# SCH_SemaforkyNG_v2_0_2023-06-26.net
KiCad netlist of a schematic drawn in EasyEDA
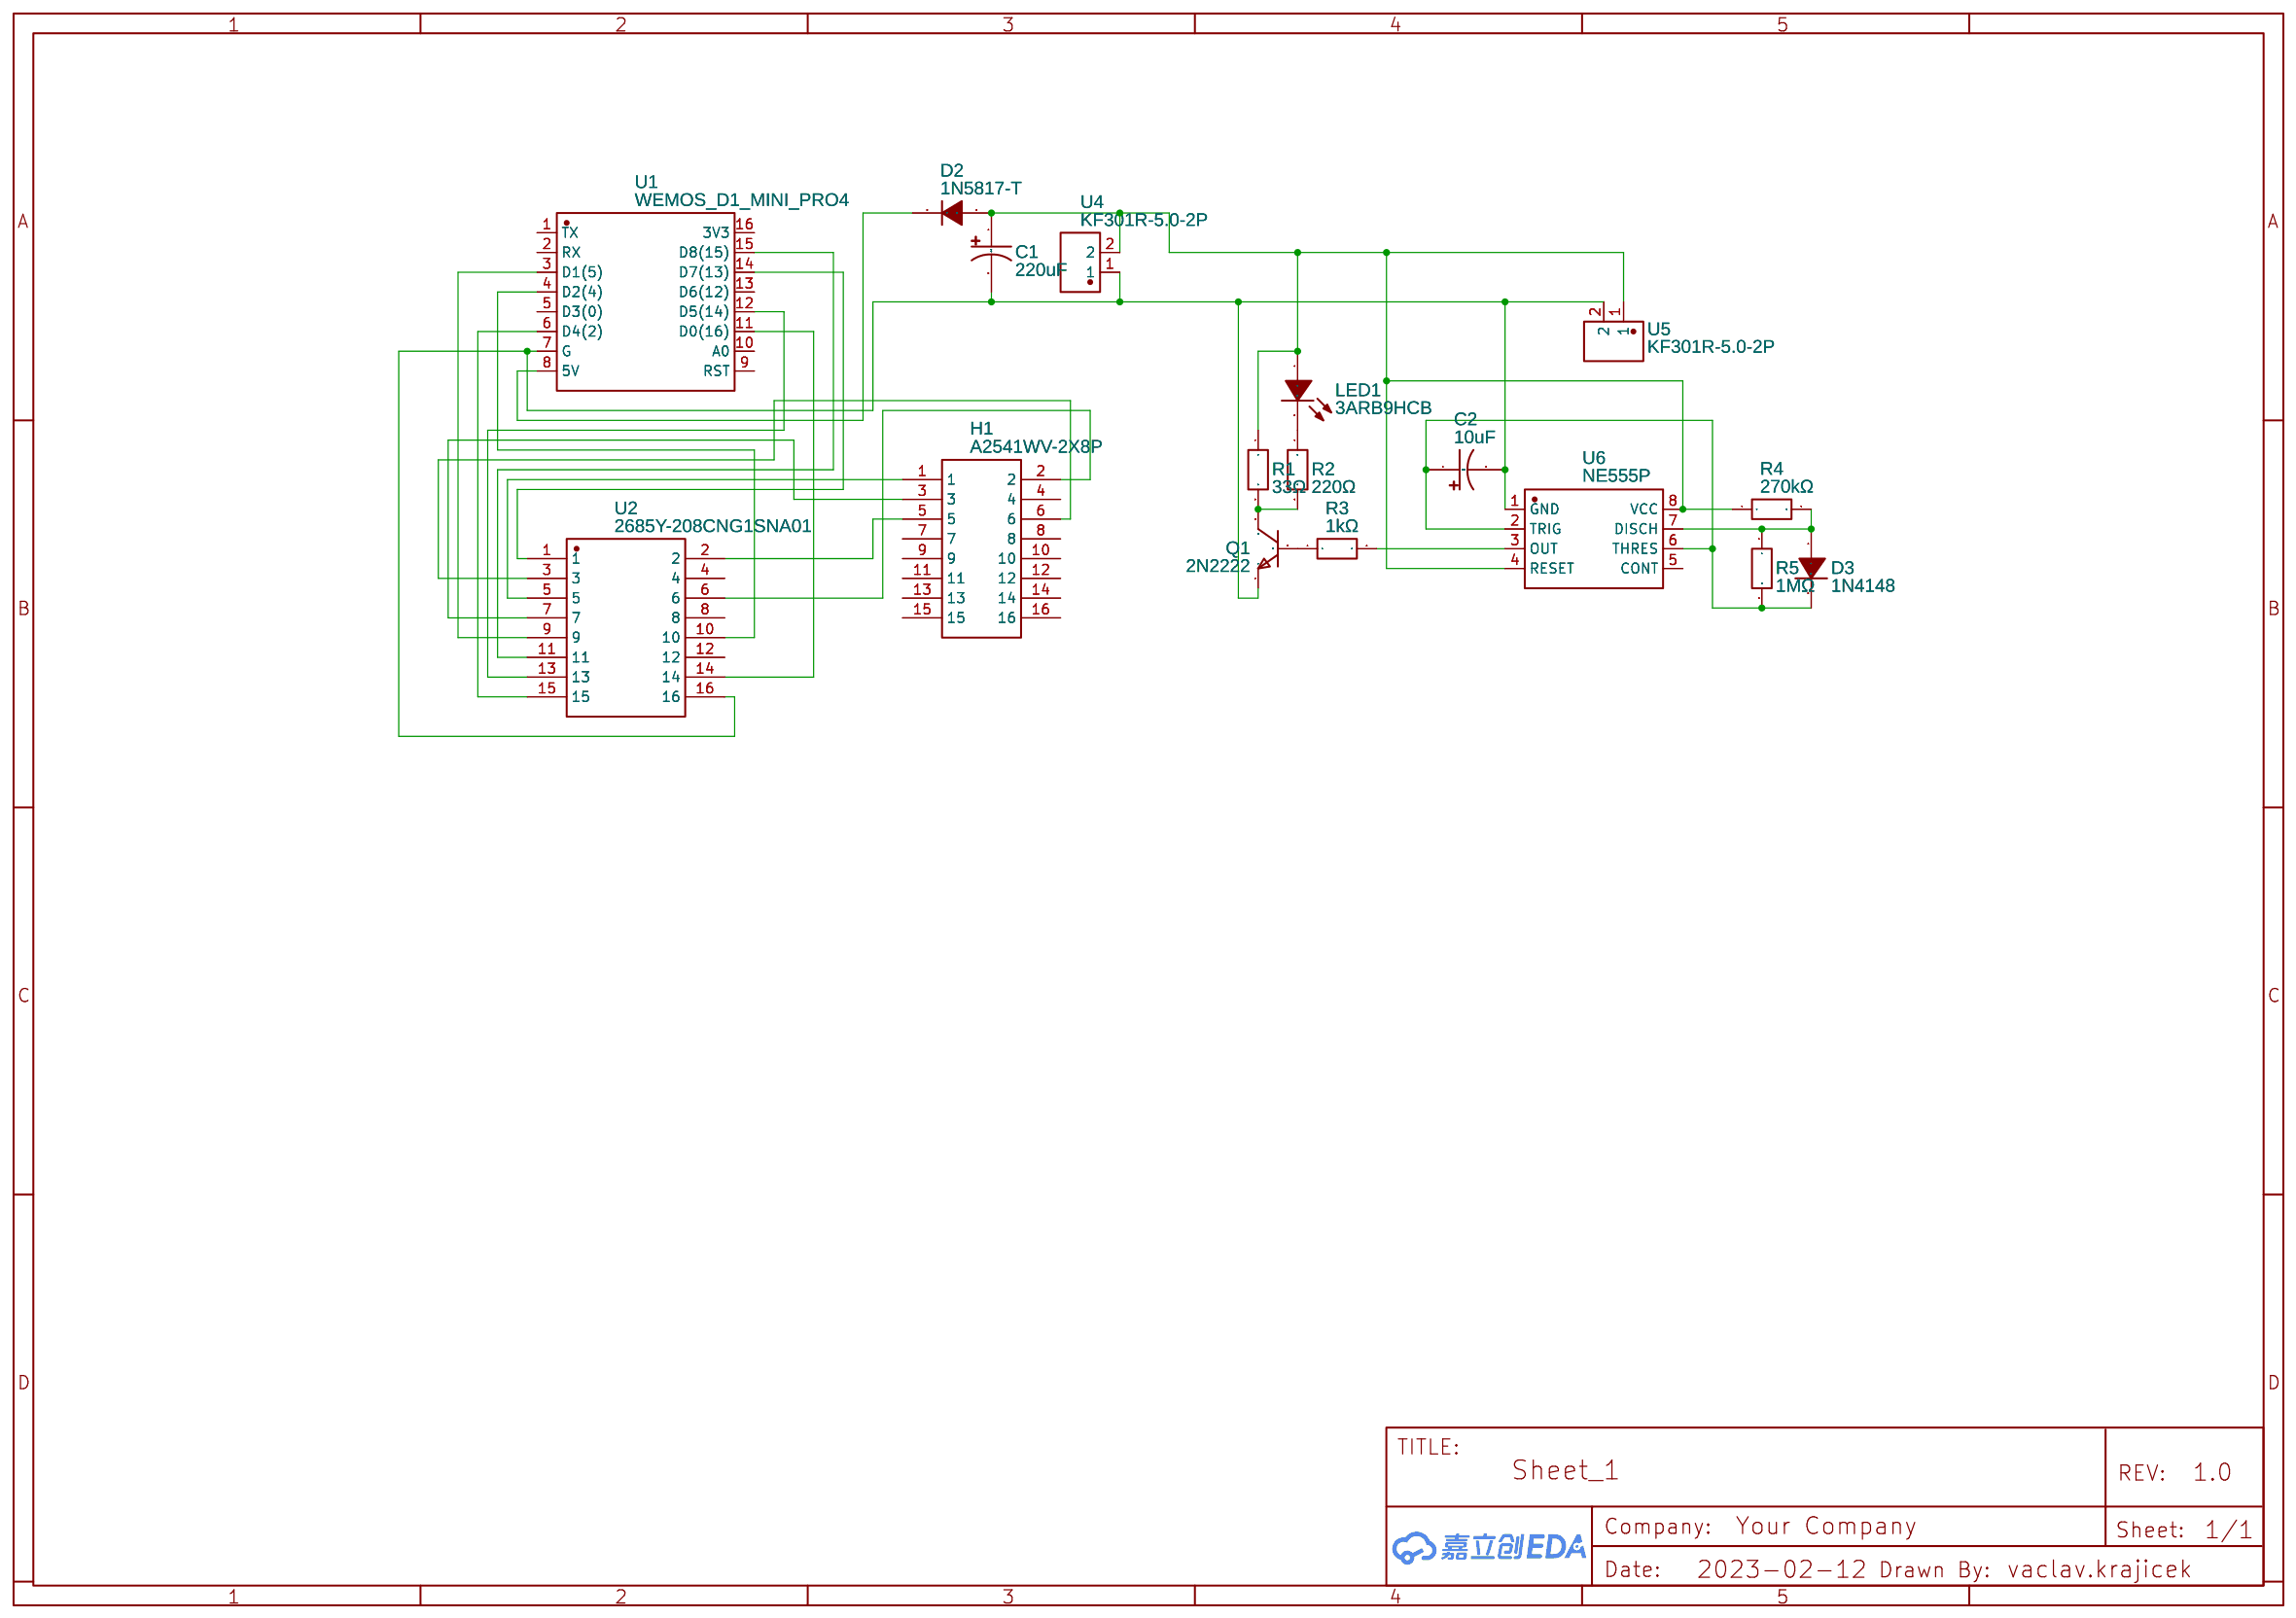
[diagram p0: schematic sheet]

(export (version "E")
  (design (tool "Eeschema 10.0.6"))
  (components
    (comp (ref "C1")
      (value "220uF")
      (fields
        (field (name "BOM_Manufacturer Part") "RC025M221LO6.3*12TH-2A1E")
        (field (name "BOM_Supplier Part") "C357621")
      )
      (libsource (lib "") (part "RC025M221LO6.3*12TH-2A1E_1"))
    )
    (comp (ref "C2")
      (value "10uF")
      (fields
        (field (name "BOM_Manufacturer Part") "RC025M221LO6.3*12TH-2A1E")
        (field (name "BOM_Supplier Part") "C357621")
      )
      (libsource (lib "") (part "RC025M221LO6.3*12TH-2A1E"))
    )
    (comp (ref "D2")
      (value "1N5817-T")
      (fields (field (name "BOM_Supplier Part") "C507852"))
      (libsource (lib "") (part "1N5817-T"))
    )
    (comp (ref "D3")
      (value "1N4148")
      (fields (field (name "BOM_Supplier Part") "C14516"))
      (libsource (lib "") (part "1N4148"))
    )
    (comp (ref "H1")
      (value "A2541WV-2X8P")
      (fields
        (field (name "BOM_Manufacturer Part") "A2541WV-2x8P")
        (field (name "BOM_Supplier Part") "C225523")
      )
      (libsource (lib "") (part "A2541WV-2X8P"))
    )
    (comp (ref "LED1")
      (value "3ARB9HCB")
      (fields (field (name "BOM_Supplier Part") "C42016"))
      (libsource (lib "") (part "3ARB9HCB"))
    )
    (comp (ref "Q1")
      (value "2N2222")
      (fields (field (name "BOM_Manufacturer Part") "2N2222A") (field (name "BOM_Supplier Part") "C118536"))
      (libsource (lib "") (part "2N2222"))
    )
    (comp (ref "R1")
      (value "33Ω")
      (fields
        (field (name "BOM_Manufacturer Part") "CR1/4W-2K2±5%-ST26")
        (field (name "BOM_Supplier Part") "C2894623")
      )
      (libsource (lib "") (part "CR1/4W-2K2±5%-ST26"))
    )
    (comp (ref "R2")
      (value "220Ω")
      (fields
        (field (name "BOM_Manufacturer Part") "CR1/4W-2K2±5%-ST26")
        (field (name "BOM_Supplier Part") "C2894623")
      )
      (libsource (lib "") (part "CR1/4W-2K2±5%-ST26"))
    )
    (comp (ref "R3")
      (value "1kΩ")
      (fields
        (field (name "BOM_Manufacturer Part") "CR1/4W-2K2±5%-ST26")
        (field (name "BOM_Supplier Part") "C2894623")
      )
      (libsource (lib "") (part "CR1/4W-2K2±5%-ST26_1"))
    )
    (comp (ref "R4")
      (value "270kΩ")
      (fields
        (field (name "BOM_Manufacturer Part") "CR1/4W-2K2±5%-ST26")
        (field (name "BOM_Supplier Part") "C2894623")
      )
      (libsource (lib "") (part "CR1/4W-2K2±5%-ST26_1"))
    )
    (comp (ref "R5")
      (value "1MΩ")
      (fields
        (field (name "BOM_Manufacturer Part") "CR1/4W-2K2±5%-ST26")
        (field (name "BOM_Supplier Part") "C2894623")
      )
      (libsource (lib "") (part "CR1/4W-2K2±5%-ST26"))
    )
    (comp (ref "U1")
      (value "WEMOS_D1_MINI_PRO4")
      (fields
        (field (name "BOM_Manufacturer Part") "Wemos_D1_mini_Pro4")
        (field (name "BOM_Supplier Part") "C2837266")
      )
      (libsource (lib "") (part "WEMOS_D1_MINI_PRO4"))
    )
    (comp (ref "U2")
      (value "2685Y-208CNG1SNA01")
      (fields (field (name "BOM_Supplier Part") "C350292"))
      (libsource (lib "") (part "2685Y-208CNG1SNA01"))
    )
    (comp (ref "U4")
      (value "KF301R-5.0-2P")
      (fields (field (name "BOM_Supplier Part") "C474883"))
      (libsource (lib "") (part "KF301R-5.0-2P"))
    )
    (comp (ref "U5")
      (value "KF301R-5.0-2P")
      (fields (field (name "BOM_Supplier Part") "C474883"))
      (libsource (lib "") (part "KF301R-5.0-2P_1"))
    )
    (comp (ref "U6")
      (value "NE555P")
      (fields (field (name "BOM_Supplier Part") "C46749"))
      (libsource (lib "") (part "NE555P"))
    )
  )
  (nets
    (net (code "1") (name "Net-(D2-A)") (class "Default")
      (node (ref "C1") (pin "1") (pinfunction "1_1") (pintype "unspecified"))
      (node (ref "D2") (pin "1") (pinfunction "A_1") (pintype "unspecified"))
      (node (ref "LED1") (pin "1") (pinfunction "A_1") (pintype "unspecified"))
      (node (ref "R1") (pin "1") (pinfunction "1_1") (pintype "unspecified"))
      (node (ref "R4") (pin "1") (pinfunction "1_1") (pintype "unspecified"))
      (node (ref "U4") (pin "2") (pinfunction "2_2") (pintype "unspecified"))
      (node (ref "U5") (pin "1") (pinfunction "1_1") (pintype "unspecified"))
      (node (ref "U6") (pin "4") (pinfunction "RESET_4") (pintype "unspecified"))
      (node (ref "U6") (pin "8") (pinfunction "VCC_8") (pintype "unspecified"))
    )
    (net (code "2") (name "Net-(D2-K)") (class "Default")
      (node (ref "D2") (pin "2") (pinfunction "K_2") (pintype "unspecified"))
      (node (ref "U1") (pin "8") (pinfunction "5V_8") (pintype "unspecified"))
    )
    (net (code "3") (name "Net-(D3-A)") (class "Default")
      (node (ref "D3") (pin "1") (pinfunction "A_1") (pintype "unspecified"))
      (node (ref "R4") (pin "2") (pinfunction "2_2") (pintype "unspecified"))
      (node (ref "R5") (pin "1") (pinfunction "1_1") (pintype "unspecified"))
      (node (ref "U6") (pin "7") (pinfunction "DISCH_7") (pintype "unspecified"))
    )
    (net (code "4") (name "Net-(D3-C)") (class "Default")
      (node (ref "C2") (pin "1") (pinfunction "1_1") (pintype "unspecified"))
      (node (ref "D3") (pin "2") (pinfunction "C_2") (pintype "unspecified"))
      (node (ref "R5") (pin "2") (pinfunction "2_2") (pintype "unspecified"))
      (node (ref "U6") (pin "2") (pinfunction "TRIG_2") (pintype "unspecified"))
      (node (ref "U6") (pin "6") (pinfunction "THRES_6") (pintype "unspecified"))
    )
    (net (code "5") (name "Net-(H1-Pad1)") (class "Default")
      (node (ref "H1") (pin "1") (pinfunction "1_1") (pintype "unspecified"))
      (node (ref "U2") (pin "5") (pinfunction "5_5") (pintype "unspecified"))
    )
    (net (code "6") (name "Net-(H1-Pad2)") (class "Default")
      (node (ref "H1") (pin "2") (pinfunction "2_2") (pintype "unspecified"))
      (node (ref "U2") (pin "6") (pinfunction "6_6") (pintype "unspecified"))
    )
    (net (code "7") (name "Net-(H1-Pad3)") (class "Default")
      (node (ref "H1") (pin "3") (pinfunction "3_3") (pintype "unspecified"))
      (node (ref "U2") (pin "7") (pinfunction "7_7") (pintype "unspecified"))
    )
    (net (code "8") (name "Net-(H1-Pad5)") (class "Default")
      (node (ref "H1") (pin "5") (pinfunction "5_5") (pintype "unspecified"))
      (node (ref "U2") (pin "2") (pinfunction "2_2") (pintype "unspecified"))
    )
    (net (code "9") (name "Net-(H1-Pad6)") (class "Default")
      (node (ref "H1") (pin "6") (pinfunction "6_6") (pintype "unspecified"))
      (node (ref "U2") (pin "3") (pinfunction "3_3") (pintype "unspecified"))
    )
    (net (code "10") (name "Net-(LED1-K)") (class "Default")
      (node (ref "LED1") (pin "2") (pinfunction "K_2") (pintype "unspecified"))
      (node (ref "R2") (pin "1") (pinfunction "1_1") (pintype "unspecified"))
    )
    (net (code "11") (name "Net-(Q1-B)") (class "Default")
      (node (ref "Q1") (pin "2") (pinfunction "B_2") (pintype "unspecified"))
      (node (ref "R3") (pin "1") (pinfunction "1_1") (pintype "unspecified"))
    )
    (net (code "12") (name "Net-(Q1-C)") (class "Default")
      (node (ref "Q1") (pin "3") (pinfunction "C_3") (pintype "unspecified"))
      (node (ref "R1") (pin "2") (pinfunction "2_2") (pintype "unspecified"))
      (node (ref "R2") (pin "2") (pinfunction "2_2") (pintype "unspecified"))
    )
    (net (code "13") (name "Net-(Q1-E)") (class "Default")
      (node (ref "C1") (pin "2") (pinfunction "2_2") (pintype "unspecified"))
      (node (ref "C2") (pin "2") (pinfunction "2_2") (pintype "unspecified"))
      (node (ref "Q1") (pin "1") (pinfunction "E_1") (pintype "unspecified"))
      (node (ref "U1") (pin "7") (pinfunction "G_7") (pintype "unspecified"))
      (node (ref "U2") (pin "16") (pinfunction "16_16") (pintype "unspecified"))
      (node (ref "U4") (pin "1") (pinfunction "1_1") (pintype "unspecified"))
      (node (ref "U5") (pin "2") (pinfunction "2_2") (pintype "unspecified"))
      (node (ref "U6") (pin "1") (pinfunction "GND_1") (pintype "unspecified"))
    )
    (net (code "14") (name "Net-(U1-D0(16))") (class "Default")
      (node (ref "U1") (pin "11") (pinfunction "D0(16)_11") (pintype "unspecified"))
      (node (ref "U2") (pin "14") (pinfunction "14_14") (pintype "unspecified"))
    )
    (net (code "15") (name "Net-(U1-D1(5))") (class "Default")
      (node (ref "U1") (pin "3") (pinfunction "D1(5)_3") (pintype "unspecified"))
      (node (ref "U2") (pin "9") (pinfunction "9_9") (pintype "unspecified"))
    )
    (net (code "16") (name "Net-(U1-D2(4))") (class "Default")
      (node (ref "U1") (pin "4") (pinfunction "D2(4)_4") (pintype "unspecified"))
      (node (ref "U2") (pin "10") (pinfunction "10_10") (pintype "unspecified"))
    )
    (net (code "17") (name "Net-(U1-D4(2))") (class "Default")
      (node (ref "U1") (pin "6") (pinfunction "D4(2)_6") (pintype "unspecified"))
      (node (ref "U2") (pin "15") (pinfunction "15_15") (pintype "unspecified"))
    )
    (net (code "18") (name "Net-(U1-D5(14))") (class "Default")
      (node (ref "U1") (pin "12") (pinfunction "D5(14)_12") (pintype "unspecified"))
      (node (ref "U2") (pin "13") (pinfunction "13_13") (pintype "unspecified"))
    )
    (net (code "19") (name "Net-(U1-D7(13))") (class "Default")
      (node (ref "U1") (pin "14") (pinfunction "D7(13)_14") (pintype "unspecified"))
      (node (ref "U2") (pin "1") (pinfunction "1_1") (pintype "unspecified"))
    )
    (net (code "20") (name "Net-(U1-D8(15))") (class "Default")
      (node (ref "U1") (pin "15") (pinfunction "D8(15)_15") (pintype "unspecified"))
      (node (ref "U2") (pin "11") (pinfunction "11_11") (pintype "unspecified"))
    )
    (net (code "21") (name "Net-(U6-OUT)") (class "Default")
      (node (ref "R3") (pin "2") (pinfunction "2_2") (pintype "unspecified"))
      (node (ref "U6") (pin "3") (pinfunction "OUT_3") (pintype "unspecified"))
    )
    (net (code "22") (name "unconnected-(H1-Pad4)") (class "Default")
      (node (ref "H1") (pin "4") (pinfunction "4_4") (pintype "unspecified"))
    )
    (net (code "23") (name "unconnected-(H1-Pad7)") (class "Default")
      (node (ref "H1") (pin "7") (pinfunction "7_7") (pintype "unspecified"))
    )
    (net (code "24") (name "unconnected-(H1-Pad8)") (class "Default")
      (node (ref "H1") (pin "8") (pinfunction "8_8") (pintype "unspecified"))
    )
    (net (code "25") (name "unconnected-(H1-Pad9)") (class "Default")
      (node (ref "H1") (pin "9") (pinfunction "9_9") (pintype "unspecified"))
    )
    (net (code "26") (name "unconnected-(H1-Pad10)") (class "Default")
      (node (ref "H1") (pin "10") (pinfunction "10_10") (pintype "unspecified"))
    )
    (net (code "27") (name "unconnected-(H1-Pad11)") (class "Default")
      (node (ref "H1") (pin "11") (pinfunction "11_11") (pintype "unspecified"))
    )
    (net (code "28") (name "unconnected-(H1-Pad12)") (class "Default")
      (node (ref "H1") (pin "12") (pinfunction "12_12") (pintype "unspecified"))
    )
    (net (code "29") (name "unconnected-(H1-Pad13)") (class "Default")
      (node (ref "H1") (pin "13") (pinfunction "13_13") (pintype "unspecified"))
    )
    (net (code "30") (name "unconnected-(H1-Pad14)") (class "Default")
      (node (ref "H1") (pin "14") (pinfunction "14_14") (pintype "unspecified"))
    )
    (net (code "31") (name "unconnected-(H1-Pad15)") (class "Default")
      (node (ref "H1") (pin "15") (pinfunction "15_15") (pintype "unspecified"))
    )
    (net (code "32") (name "unconnected-(H1-Pad16)") (class "Default")
      (node (ref "H1") (pin "16") (pinfunction "16_16") (pintype "unspecified"))
    )
    (net (code "33") (name "unconnected-(U1-3V3-Pad16)") (class "Default")
      (node (ref "U1") (pin "16") (pinfunction "3V3_16") (pintype "unspecified"))
    )
    (net (code "34") (name "unconnected-(U1-A0-Pad10)") (class "Default")
      (node (ref "U1") (pin "10") (pinfunction "A0_10") (pintype "unspecified"))
    )
    (net (code "35") (name "unconnected-(U1-D3(0)-Pad5)") (class "Default")
      (node (ref "U1") (pin "5") (pinfunction "D3(0)_5") (pintype "unspecified"))
    )
    (net (code "36") (name "unconnected-(U1-D6(12)-Pad13)") (class "Default")
      (node (ref "U1") (pin "13") (pinfunction "D6(12)_13") (pintype "unspecified"))
    )
    (net (code "37") (name "unconnected-(U1-RST-Pad9)") (class "Default")
      (node (ref "U1") (pin "9") (pinfunction "RST_9") (pintype "unspecified"))
    )
    (net (code "38") (name "unconnected-(U1-RX-Pad2)") (class "Default")
      (node (ref "U1") (pin "2") (pinfunction "RX_2") (pintype "unspecified"))
    )
    (net (code "39") (name "unconnected-(U1-TX-Pad1)") (class "Default")
      (node (ref "U1") (pin "1") (pinfunction "TX_1") (pintype "unspecified"))
    )
    (net (code "40") (name "unconnected-(U2-Pad4)") (class "Default")
      (node (ref "U2") (pin "4") (pinfunction "4_4") (pintype "unspecified"))
    )
    (net (code "41") (name "unconnected-(U2-Pad8)") (class "Default")
      (node (ref "U2") (pin "8") (pinfunction "8_8") (pintype "unspecified"))
    )
    (net (code "42") (name "unconnected-(U2-Pad12)") (class "Default")
      (node (ref "U2") (pin "12") (pinfunction "12_12") (pintype "unspecified"))
    )
    (net (code "43") (name "unconnected-(U6-CONT-Pad5)") (class "Default")
      (node (ref "U6") (pin "5") (pinfunction "CONT_5") (pintype "unspecified"))
    )
  )
)
